# CoolShield.net
KiCad netlist of a schematic drawn in EAGLE
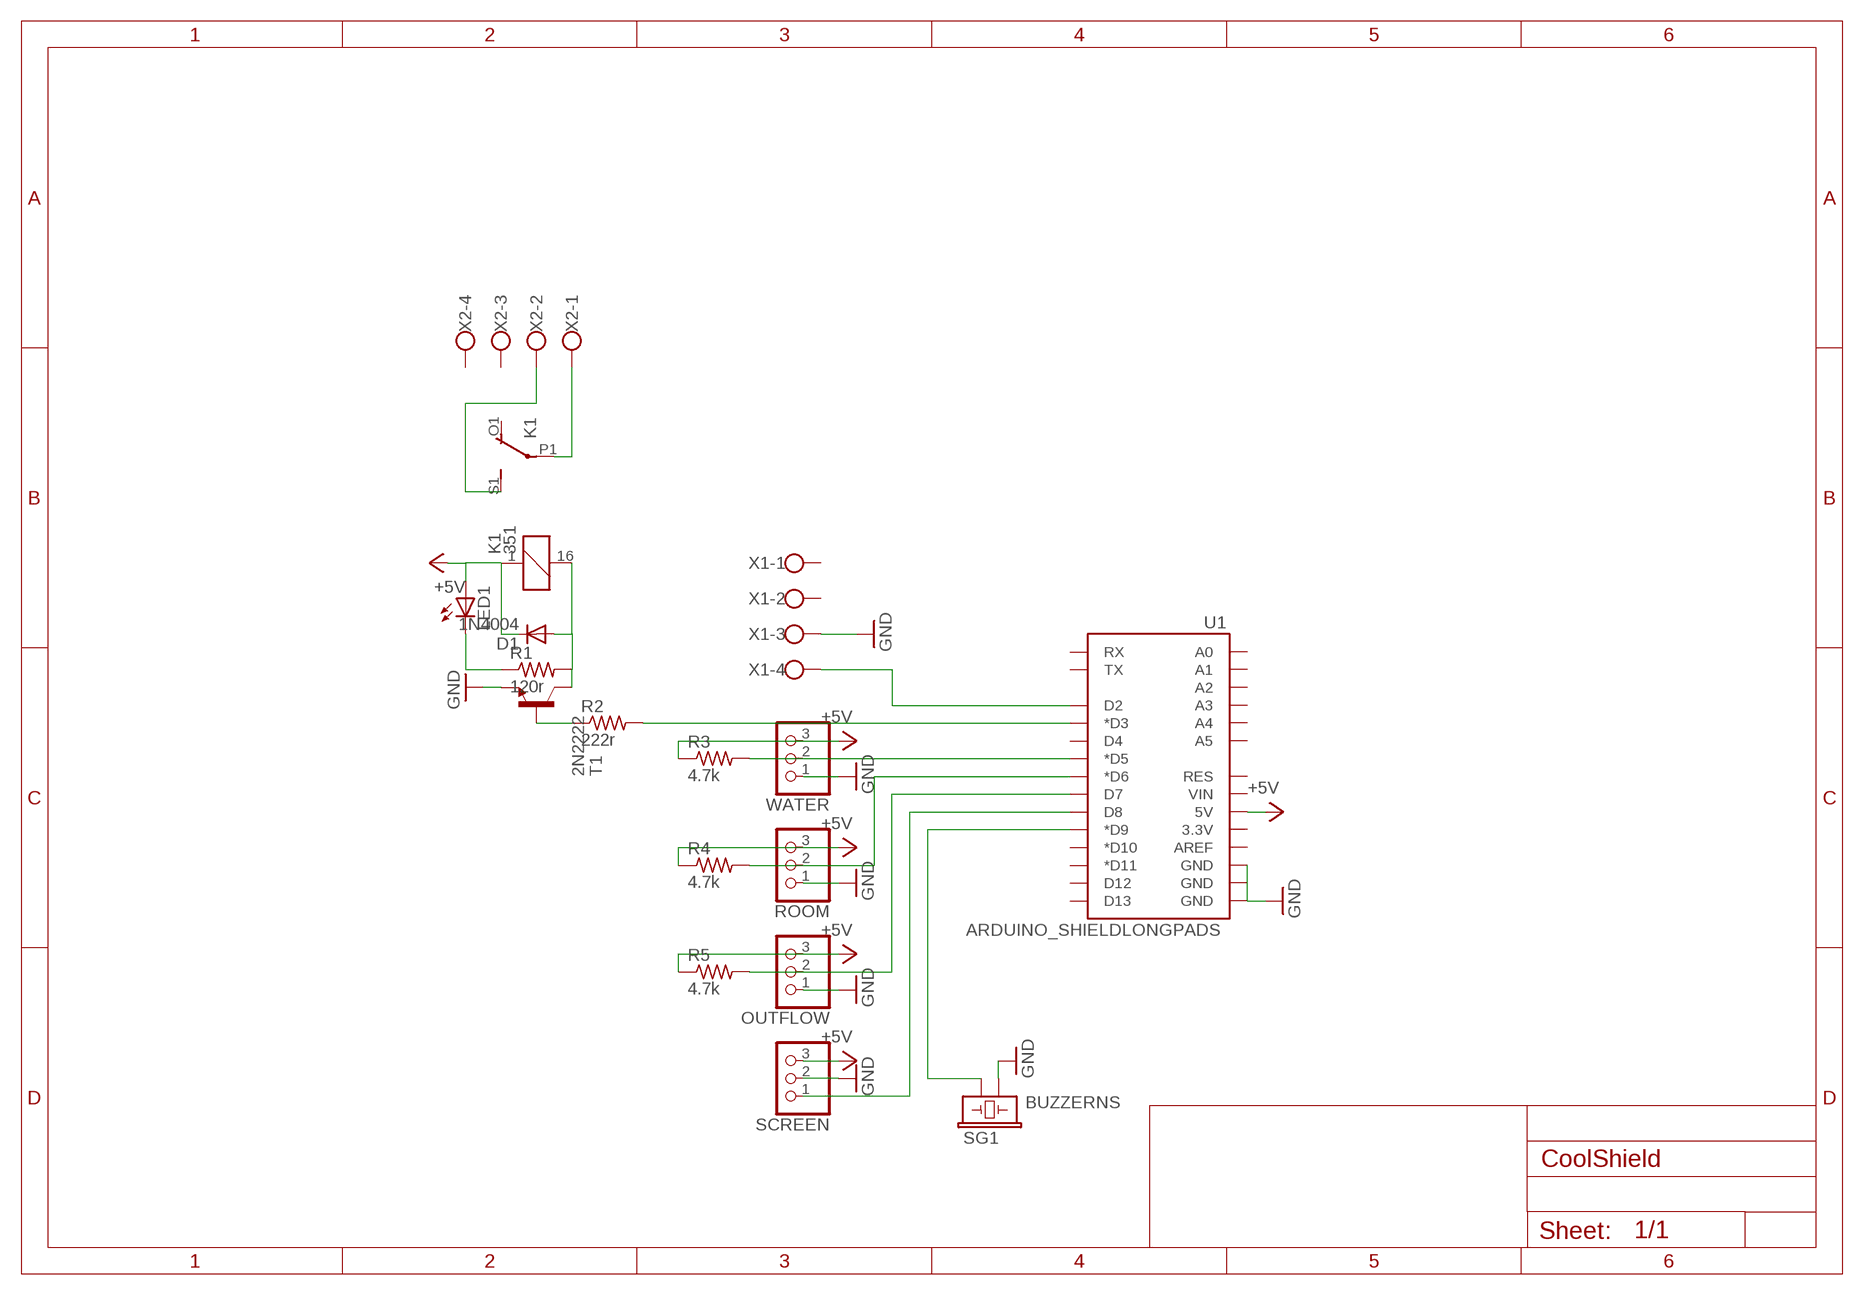
[diagram p0: schematic, sheet 1]

(export (version "E")
  (design (tool "Eeschema 10.0.6"))
  (components
    (comp (ref "D1")
      (value "1N4004")
      (footprint "eagle-import:DO41-10")
      (libsource (lib "eagle-import") (part "1N4004"))
    )
    (comp (ref "K1")
      (value "351")
      (footprint "eagle-import:351")
      (libsource (lib "eagle-import") (part "351"))
    )
    (comp (ref "LED1")
      (value "LED5MM")
      (footprint "eagle-import:LED5MM")
      (libsource (lib "eagle-import") (part "LED5MM"))
    )
    (comp (ref "OUTFLOW")
      (value "PINHD-1X3")
      (footprint "eagle-import:1X03")
      (libsource (lib "eagle-import") (part "PINHD-1X3"))
    )
    (comp (ref "R1")
      (value "120r")
      (footprint "eagle-import:0204_7")
      (libsource (lib "eagle-import") (part "R-US_0204/7"))
    )
    (comp (ref "R2")
      (value "222r")
      (footprint "eagle-import:0204_7")
      (libsource (lib "eagle-import") (part "R-US_0204/7"))
    )
    (comp (ref "R3")
      (value "4.7k")
      (footprint "eagle-import:0204_7")
      (libsource (lib "eagle-import") (part "R-US_0204/7"))
    )
    (comp (ref "R4")
      (value "4.7k")
      (footprint "eagle-import:0204_7")
      (libsource (lib "eagle-import") (part "R-US_0204/7"))
    )
    (comp (ref "R5")
      (value "4.7k")
      (footprint "eagle-import:0204_7")
      (libsource (lib "eagle-import") (part "R-US_0204/7"))
    )
    (comp (ref "ROOM")
      (value "PINHD-1X3")
      (footprint "eagle-import:1X03")
      (libsource (lib "eagle-import") (part "PINHD-1X3"))
    )
    (comp (ref "SCREEN")
      (value "PINHD-1X3")
      (footprint "eagle-import:1X03")
      (libsource (lib "eagle-import") (part "PINHD-1X3"))
    )
    (comp (ref "SG1")
      (value "BUZZERNS")
      (footprint "eagle-import:BUZZER-12MM-NS")
      (libsource (lib "eagle-import") (part "BUZZERNS"))
    )
    (comp (ref "T1")
      (value "2N2222")
      (footprint "eagle-import:TO92-EBC-OVAL")
      (libsource (lib "eagle-import") (part "2N2222"))
    )
    (comp (ref "U1")
      (value "ARDUINO_SHIELDLONGPADS")
      (footprint "eagle-import:DUEMILANOVE_SHIELD_LONGPADS")
      (libsource (lib "eagle-import") (part "ARDUINO_SHIELDLONGPADS"))
    )
    (comp (ref "WATER")
      (value "PINHD-1X3")
      (footprint "eagle-import:1X03")
      (libsource (lib "eagle-import") (part "PINHD-1X3"))
    )
    (comp (ref "X1")
      (value "W237-4")
      (footprint "eagle-import:W237-4")
      (libsource (lib "eagle-import") (part "W237-4"))
    )
    (comp (ref "X2")
      (value "W237-4")
      (footprint "eagle-import:W237-4")
      (libsource (lib "eagle-import") (part "W237-4"))
    )
  )
  (nets
    (net (code "1") (name "+5V") (class "Default")
      (node (ref "D1") (pin "C") (pinfunction "C_C") (pintype "passive"))
      (node (ref "K1") (pin "1") (pinfunction "1_1") (pintype "passive"))
      (node (ref "LED1") (pin "A") (pinfunction "A_A") (pintype "passive"))
      (node (ref "OUTFLOW") (pin "3") (pinfunction "3_3") (pintype "passive"))
      (node (ref "R3") (pin "1") (pinfunction "1_1") (pintype "passive"))
      (node (ref "R4") (pin "1") (pinfunction "1_1") (pintype "passive"))
      (node (ref "R5") (pin "1") (pinfunction "1_1") (pintype "passive"))
      (node (ref "ROOM") (pin "3") (pinfunction "3_3") (pintype "passive"))
      (node (ref "SCREEN") (pin "3") (pinfunction "3_3") (pintype "passive"))
      (node (ref "U1") (pin "5V") (pinfunction "5V_5V") (pintype "bidirectional"))
      (node (ref "WATER") (pin "3") (pinfunction "3_3") (pintype "passive"))
    )
    (net (code "2") (name "GND") (class "Default")
      (node (ref "OUTFLOW") (pin "1") (pinfunction "1_1") (pintype "passive"))
      (node (ref "ROOM") (pin "1") (pinfunction "1_1") (pintype "passive"))
      (node (ref "SCREEN") (pin "2") (pinfunction "2_2") (pintype "passive"))
      (node (ref "SG1") (pin "-") (pinfunction "2_-") (pintype "passive"))
      (node (ref "T1") (pin "E") (pinfunction "E_E") (pintype "passive"))
      (node (ref "U1") (pin "GND@0") (pinfunction "GND_GND@0") (pintype "bidirectional"))
      (node (ref "U1") (pin "GND@1") (pinfunction "GND_GND@1") (pintype "bidirectional"))
      (node (ref "U1") (pin "GND@2") (pinfunction "GND_GND@2") (pintype "bidirectional"))
      (node (ref "WATER") (pin "1") (pinfunction "1_1") (pintype "passive"))
      (node (ref "X1") (pin "3") (pinfunction "KL_3") (pintype "passive"))
    )
    (net (code "3") (name "Net-(K1A-2)") (class "Default")
      (node (ref "D1") (pin "A") (pinfunction "A_A") (pintype "passive"))
      (node (ref "K1") (pin "16") (pinfunction "2_16") (pintype "passive"))
      (node (ref "R1") (pin "2") (pinfunction "2_2") (pintype "passive"))
      (node (ref "T1") (pin "C") (pinfunction "C_C") (pintype "passive"))
    )
    (net (code "4") (name "Net-(K1B-P)") (class "Default")
      (node (ref "K1") (pin "P1") (pinfunction "P_P1") (pintype "passive"))
      (node (ref "X2") (pin "1") (pinfunction "KL_1") (pintype "passive"))
    )
    (net (code "5") (name "Net-(K1B-S)") (class "Default")
      (node (ref "K1") (pin "S1") (pinfunction "S_S1") (pintype "passive"))
      (node (ref "X2") (pin "2") (pinfunction "KL_2") (pintype "passive"))
    )
    (net (code "6") (name "Net-(LED1-C)") (class "Default")
      (node (ref "LED1") (pin "K") (pinfunction "C_K") (pintype "passive"))
      (node (ref "R1") (pin "1") (pinfunction "1_1") (pintype "passive"))
    )
    (net (code "7") (name "Net-(OUTFLOW-Pad2)") (class "Default")
      (node (ref "OUTFLOW") (pin "2") (pinfunction "2_2") (pintype "passive"))
      (node (ref "R5") (pin "2") (pinfunction "2_2") (pintype "passive"))
      (node (ref "U1") (pin "D7") (pinfunction "D7_D7") (pintype "bidirectional"))
    )
    (net (code "8") (name "Net-(R2-Pad1)") (class "Default")
      (node (ref "R2") (pin "1") (pinfunction "1_1") (pintype "passive"))
      (node (ref "T1") (pin "B") (pinfunction "B_B") (pintype "passive"))
    )
    (net (code "9") (name "Net-(SCREEN-Pad1)") (class "Default")
      (node (ref "SCREEN") (pin "1") (pinfunction "1_1") (pintype "passive"))
      (node (ref "U1") (pin "D8") (pinfunction "D8_D8") (pintype "bidirectional"))
    )
    (net (code "10") (name "Net-(SG1-1)") (class "Default")
      (node (ref "SG1") (pin "+") (pinfunction "1_+") (pintype "passive"))
      (node (ref "U1") (pin "D9") (pinfunction "*D9_D9") (pintype "bidirectional"))
    )
    (net (code "11") (name "Net-(U1-*D3)") (class "Default")
      (node (ref "R2") (pin "2") (pinfunction "2_2") (pintype "passive"))
      (node (ref "U1") (pin "D3") (pinfunction "*D3_D3") (pintype "bidirectional"))
    )
    (net (code "12") (name "Net-(U1-*D5)") (class "Default")
      (node (ref "R3") (pin "2") (pinfunction "2_2") (pintype "passive"))
      (node (ref "U1") (pin "D5") (pinfunction "*D5_D5") (pintype "bidirectional"))
      (node (ref "WATER") (pin "2") (pinfunction "2_2") (pintype "passive"))
    )
    (net (code "13") (name "Net-(U1-*D6)") (class "Default")
      (node (ref "R4") (pin "2") (pinfunction "2_2") (pintype "passive"))
      (node (ref "ROOM") (pin "2") (pinfunction "2_2") (pintype "passive"))
      (node (ref "U1") (pin "D6") (pinfunction "*D6_D6") (pintype "bidirectional"))
    )
    (net (code "14") (name "Net-(X1D-KL)") (class "Default")
      (node (ref "U1") (pin "D2") (pinfunction "D2_D2") (pintype "bidirectional"))
      (node (ref "X1") (pin "4") (pinfunction "KL_4") (pintype "passive"))
    )
    (net (code "15") (name "unconnected-(K1B-O-PadO1)") (class "Default")
      (node (ref "K1") (pin "O1") (pinfunction "O_O1") (pintype "passive"))
    )
    (net (code "16") (name "unconnected-(U1-*D10-PadD10)") (class "Default")
      (node (ref "U1") (pin "D10") (pinfunction "*D10_D10") (pintype "bidirectional"))
    )
    (net (code "17") (name "unconnected-(U1-*D11-PadD11)") (class "Default")
      (node (ref "U1") (pin "D11") (pinfunction "*D11_D11") (pintype "bidirectional"))
    )
    (net (code "18") (name "unconnected-(U1-Pad3.3V)") (class "Default")
      (node (ref "U1") (pin "3.3V") (pinfunction "3.3V_3.3V") (pintype "bidirectional"))
    )
    (net (code "19") (name "unconnected-(U1-PadA0)") (class "Default")
      (node (ref "U1") (pin "A0") (pinfunction "A0_A0") (pintype "bidirectional"))
    )
    (net (code "20") (name "unconnected-(U1-PadA1)") (class "Default")
      (node (ref "U1") (pin "A1") (pinfunction "A1_A1") (pintype "bidirectional"))
    )
    (net (code "21") (name "unconnected-(U1-PadA2)") (class "Default")
      (node (ref "U1") (pin "A2") (pinfunction "A2_A2") (pintype "bidirectional"))
    )
    (net (code "22") (name "unconnected-(U1-PadA3)") (class "Default")
      (node (ref "U1") (pin "A3") (pinfunction "A3_A3") (pintype "bidirectional"))
    )
    (net (code "23") (name "unconnected-(U1-PadA4)") (class "Default")
      (node (ref "U1") (pin "A4") (pinfunction "A4_A4") (pintype "bidirectional"))
    )
    (net (code "24") (name "unconnected-(U1-PadA5)") (class "Default")
      (node (ref "U1") (pin "A5") (pinfunction "A5_A5") (pintype "bidirectional"))
    )
    (net (code "25") (name "unconnected-(U1-PadAREF)") (class "Default")
      (node (ref "U1") (pin "AREF") (pinfunction "AREF_AREF") (pintype "bidirectional"))
    )
    (net (code "26") (name "unconnected-(U1-PadD4)") (class "Default")
      (node (ref "U1") (pin "D4") (pinfunction "D4_D4") (pintype "bidirectional"))
    )
    (net (code "27") (name "unconnected-(U1-PadD12)") (class "Default")
      (node (ref "U1") (pin "D12") (pinfunction "D12_D12") (pintype "bidirectional"))
    )
    (net (code "28") (name "unconnected-(U1-PadD13)") (class "Default")
      (node (ref "U1") (pin "D13") (pinfunction "D13_D13") (pintype "bidirectional"))
    )
    (net (code "29") (name "unconnected-(U1-PadRES)") (class "Default")
      (node (ref "U1") (pin "RES") (pinfunction "RES_RES") (pintype "bidirectional"))
    )
    (net (code "30") (name "unconnected-(U1-PadRX)") (class "Default")
      (node (ref "U1") (pin "RX") (pinfunction "RX_RX") (pintype "bidirectional"))
    )
    (net (code "31") (name "unconnected-(U1-PadTX)") (class "Default")
      (node (ref "U1") (pin "TX") (pinfunction "TX_TX") (pintype "bidirectional"))
    )
    (net (code "32") (name "unconnected-(U1-PadVIN)") (class "Default")
      (node (ref "U1") (pin "VIN") (pinfunction "VIN_VIN") (pintype "bidirectional"))
    )
    (net (code "33") (name "unconnected-(X1A-KL-Pad1)") (class "Default")
      (node (ref "X1") (pin "1") (pinfunction "KL_1") (pintype "passive"))
    )
    (net (code "34") (name "unconnected-(X1B-KL-Pad2)") (class "Default")
      (node (ref "X1") (pin "2") (pinfunction "KL_2") (pintype "passive"))
    )
    (net (code "35") (name "unconnected-(X2C-KL-Pad3)") (class "Default")
      (node (ref "X2") (pin "3") (pinfunction "KL_3") (pintype "passive"))
    )
    (net (code "36") (name "unconnected-(X2D-KL-Pad4)") (class "Default")
      (node (ref "X2") (pin "4") (pinfunction "KL_4") (pintype "passive"))
    )
  )
)
